# OMD_LEDS_2_wire.net
KiCad netlist of a schematic drawn in Altium Designer
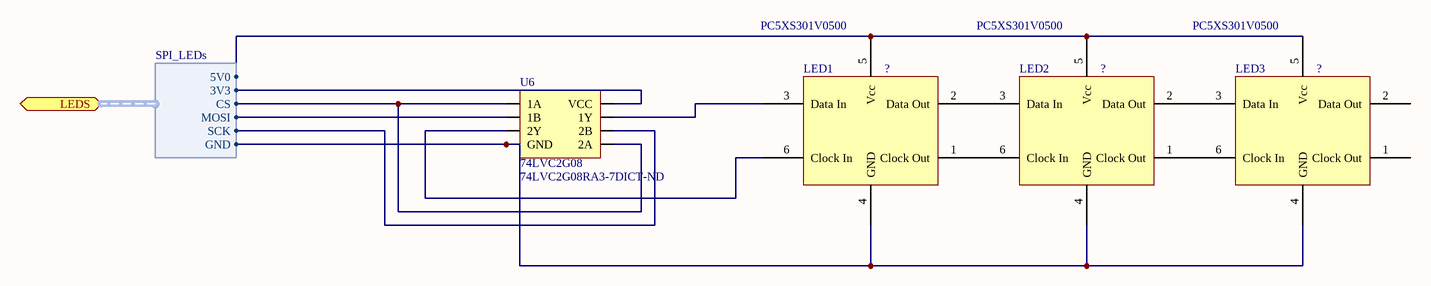
[diagram p0: OMD_LEDS_2_wire.SchDoc]

(export (version "E")
  (design (tool "Eeschema 10.0.6"))
  (components
    (comp (ref "LED1")
      (value "?")
      (footprint "UBLED")
      (fields
        (field (name "SUPPLIER PART NUMBER 1") "PC5XS301V0500")
        (field (name "SUPPLIER 1") "jeff_chang@ubleds.com.tw")
      )
      (libsource (lib "ProfiCNC") (part "UBLED"))
    )
    (comp (ref "LED2")
      (value "?")
      (footprint "UBLED")
      (fields
        (field (name "SUPPLIER PART NUMBER 1") "PC5XS301V0500")
        (field (name "SUPPLIER 1") "jeff_chang@ubleds.com.tw")
      )
      (libsource (lib "ProfiCNC") (part "UBLED"))
    )
    (comp (ref "LED3")
      (value "?")
      (footprint "UBLED")
      (fields
        (field (name "SUPPLIER PART NUMBER 1") "PC5XS301V0500")
        (field (name "SUPPLIER 1") "jeff_chang@ubleds.com.tw")
      )
      (libsource (lib "ProfiCNC") (part "UBLED"))
    )
    (comp (ref "U6")
      (value "74LVC2G08")
      (footprint "SON50P100X40_HS-9L")
      (fields (field (name "SUPPLIER PART NUMBER 1") "74LVC2G08RA3-7DICT-ND"))
      (libsource (lib "SOLO_CAN") (part "74LVC2G08"))
    )
  )
  (nets
    (net (code "2") (name "/3V3") (class "Default")
      (node (ref "U6") (pin "8") (pinfunction "VCC_8") (pintype "passive"))
    )
    (net (code "3") (name "/5V0") (class "Default")
      (node (ref "LED1") (pin "5") (pinfunction "Vcc_5") (pintype "passive"))
      (node (ref "LED2") (pin "5") (pinfunction "Vcc_5") (pintype "passive"))
      (node (ref "LED3") (pin "5") (pinfunction "Vcc_5") (pintype "passive"))
    )
    (net (code "4") (name "/CS") (class "Default")
      (node (ref "U6") (pin "1") (pinfunction "1A_1") (pintype "passive"))
      (node (ref "U6") (pin "5") (pinfunction "2A_5") (pintype "passive"))
    )
    (net (code "5") (name "/GND") (class "Default")
      (node (ref "LED1") (pin "4") (pinfunction "GND_4") (pintype "passive"))
      (node (ref "LED2") (pin "4") (pinfunction "GND_4") (pintype "passive"))
      (node (ref "LED3") (pin "4") (pinfunction "GND_4") (pintype "passive"))
      (node (ref "U6") (pin "4") (pinfunction "GND_4") (pintype "passive"))
    )
    (net (code "6") (name "/MOSI") (class "Default")
      (node (ref "U6") (pin "2") (pinfunction "1B_2") (pintype "passive"))
    )
    (net (code "7") (name "/SCK") (class "Default")
      (node (ref "U6") (pin "6") (pinfunction "2B_6") (pintype "passive"))
    )
    (net (code "9") (name "Net-(LED1-Clock_In)") (class "Default")
      (node (ref "LED1") (pin "6") (pinfunction "Clock_In_6") (pintype "passive"))
      (node (ref "U6") (pin "3") (pinfunction "2Y_3") (pintype "passive"))
    )
    (net (code "10") (name "Net-(LED1-Clock_Out)") (class "Default")
      (node (ref "LED1") (pin "1") (pinfunction "Clock_Out_1") (pintype "passive"))
      (node (ref "LED2") (pin "6") (pinfunction "Clock_In_6") (pintype "passive"))
    )
    (net (code "11") (name "Net-(LED1-Data_In)") (class "Default")
      (node (ref "LED1") (pin "3") (pinfunction "Data_In_3") (pintype "passive"))
      (node (ref "U6") (pin "7") (pinfunction "1Y_7") (pintype "passive"))
    )
    (net (code "12") (name "Net-(LED1-Data_Out)") (class "Default")
      (node (ref "LED1") (pin "2") (pinfunction "Data_Out_2") (pintype "passive"))
      (node (ref "LED2") (pin "3") (pinfunction "Data_In_3") (pintype "passive"))
    )
    (net (code "13") (name "Net-(LED2-Clock_Out)") (class "Default")
      (node (ref "LED2") (pin "1") (pinfunction "Clock_Out_1") (pintype "passive"))
      (node (ref "LED3") (pin "6") (pinfunction "Clock_In_6") (pintype "passive"))
    )
    (net (code "14") (name "Net-(LED2-Data_Out)") (class "Default")
      (node (ref "LED2") (pin "2") (pinfunction "Data_Out_2") (pintype "passive"))
      (node (ref "LED3") (pin "3") (pinfunction "Data_In_3") (pintype "passive"))
    )
    (net (code "15") (name "unconnected-(LED3-Clock_Out-Pad1)") (class "Default")
      (node (ref "LED3") (pin "1") (pinfunction "Clock_Out_1") (pintype "passive"))
    )
    (net (code "16") (name "unconnected-(LED3-Data_Out-Pad2)") (class "Default")
      (node (ref "LED3") (pin "2") (pinfunction "Data_Out_2") (pintype "passive"))
    )
  )
)
